# 328vusb.net
KiCad netlist of a schematic drawn in EAGLE
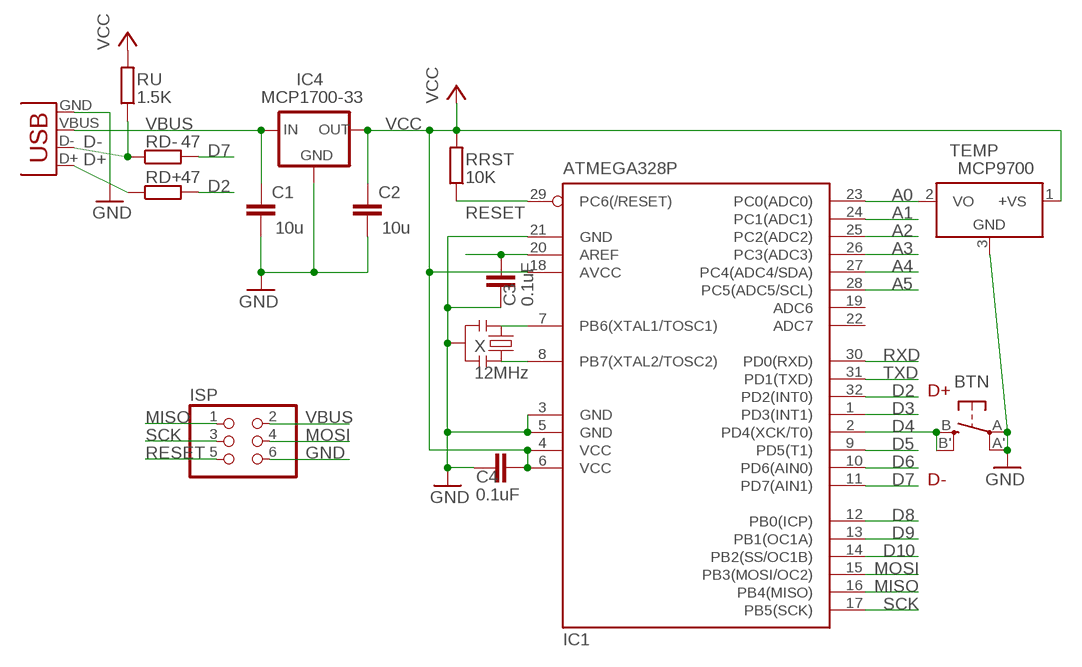
[diagram p0: schematic, sheet 1]

(export (version "E")
  (design (tool "Eeschema 10.0.6"))
  (components
    (comp (ref "BTN")
      (value "EVQQ2")
      (footprint "eagle-import:EVQ-Q2")
      (libsource (lib "eagle-import") (part "EVQQ2"))
    )
    (comp (ref "C1")
      (value "10u")
      (footprint "eagle-import:C0805")
      (libsource (lib "eagle-import") (part "resistor_C-EUC0805"))
    )
    (comp (ref "C2")
      (value "10u")
      (footprint "eagle-import:C0805")
      (libsource (lib "eagle-import") (part "resistor_C-EUC0805"))
    )
    (comp (ref "C3")
      (value "0.1uF")
      (footprint "eagle-import:C0805")
      (libsource (lib "eagle-import") (part "C-EUC0805"))
    )
    (comp (ref "C4")
      (value "0.1uF")
      (footprint "eagle-import:C0805")
      (libsource (lib "eagle-import") (part "C-EUC0805"))
    )
    (comp (ref "IC1")
      (value "ATMEGA328P")
      (footprint "eagle-import:TQFP32-08")
      (fields (field (name "MPN") "ATMEGA8-16AU"))
      (libsource (lib "eagle-import") (part "MEGA8-AI"))
    )
    (comp (ref "IC4")
      (value "MCP1700-33")
      (footprint "eagle-import:SOT23")
      (libsource (lib "eagle-import") (part "MCP1700SOT233"))
    )
    (comp (ref "ISP")
      (value "PINHD-2X3")
      (footprint "eagle-import:2X03")
      (libsource (lib "eagle-import") (part "PINHD-2X3"))
    )
    (comp (ref "RD+")
      (value "47")
      (footprint "eagle-import:R0805")
      (libsource (lib "eagle-import") (part "R-EU_R0805"))
    )
    (comp (ref "RD-")
      (value "47")
      (footprint "eagle-import:R0805")
      (libsource (lib "eagle-import") (part "R-EU_R0805"))
    )
    (comp (ref "RRST")
      (value "10K")
      (footprint "eagle-import:R0805")
      (libsource (lib "eagle-import") (part "R-EU_R0805"))
    )
    (comp (ref "RU")
      (value "1.5K")
      (footprint "eagle-import:R0805")
      (libsource (lib "eagle-import") (part "R-EU_R0805"))
    )
    (comp (ref "TEMP")
      (value "MCP9700")
      (footprint "eagle-import:SOT23")
      (libsource (lib "eagle-import") (part "LM50"))
    )
    (comp (ref "X")
      (value "12MHz")
      (footprint "eagle-import:RESONATOR-SMD")
      (libsource (lib "eagle-import") (part "RESONATORSMD"))
    )
    (comp (ref "X1")
      (value "USBSMD")
      (footprint "eagle-import:USB-MINIB")
      (libsource (lib "eagle-import") (part "USBSMD"))
    )
  )
  (nets
    (net (code "1") (name "/A0") (class "Default")
      (node (ref "IC1") (pin "23") (pinfunction "PC0(ADC0)_23") (pintype "bidirectional"))
      (node (ref "TEMP") (pin "2") (pinfunction "VO_2") (pintype "input"))
    )
    (net (code "2") (name "/A1") (class "Default")
      (node (ref "IC1") (pin "24") (pinfunction "PC1(ADC1)_24") (pintype "bidirectional"))
    )
    (net (code "3") (name "/A2") (class "Default")
      (node (ref "IC1") (pin "25") (pinfunction "PC2(ADC2)_25") (pintype "bidirectional"))
    )
    (net (code "4") (name "/A3") (class "Default")
      (node (ref "IC1") (pin "26") (pinfunction "PC3(ADC3)_26") (pintype "bidirectional"))
    )
    (net (code "5") (name "/A4") (class "Default")
      (node (ref "IC1") (pin "27") (pinfunction "PC4(ADC4/SDA)_27") (pintype "bidirectional"))
    )
    (net (code "6") (name "/A5") (class "Default")
      (node (ref "IC1") (pin "28") (pinfunction "PC5(ADC5/SCL)_28") (pintype "bidirectional"))
    )
    (net (code "7") (name "/D+") (class "Default")
      (node (ref "RD+") (pin "1") (pinfunction "1_1") (pintype "passive"))
      (node (ref "X1") (pin "D+") (pinfunction "D+_D+") (pintype "bidirectional"))
    )
    (net (code "8") (name "/D-") (class "Default")
      (node (ref "RD-") (pin "1") (pinfunction "1_1") (pintype "passive"))
      (node (ref "RU") (pin "1") (pinfunction "1_1") (pintype "passive"))
      (node (ref "X1") (pin "D-") (pinfunction "D-_D-") (pintype "bidirectional"))
    )
    (net (code "9") (name "/D2") (class "Default")
      (node (ref "IC1") (pin "32") (pinfunction "PD2(INT0)_32") (pintype "bidirectional"))
      (node (ref "RD+") (pin "2") (pinfunction "2_2") (pintype "passive"))
    )
    (net (code "10") (name "/D3") (class "Default")
      (node (ref "IC1") (pin "1") (pinfunction "PD3(INT1)_1") (pintype "bidirectional"))
    )
    (net (code "11") (name "/D4") (class "Default")
      (node (ref "BTN") (pin "B") (pinfunction "S_B") (pintype "passive"))
      (node (ref "BTN") (pin "B'") (pinfunction "S1_B'") (pintype "passive"))
      (node (ref "IC1") (pin "2") (pinfunction "PD4(XCK/T0)_2") (pintype "bidirectional"))
    )
    (net (code "12") (name "/D5") (class "Default")
      (node (ref "IC1") (pin "9") (pinfunction "PD5(T1)_9") (pintype "bidirectional"))
    )
    (net (code "13") (name "/D6") (class "Default")
      (node (ref "IC1") (pin "10") (pinfunction "PD6(AIN0)_10") (pintype "bidirectional"))
    )
    (net (code "14") (name "/D7") (class "Default")
      (node (ref "IC1") (pin "11") (pinfunction "PD7(AIN1)_11") (pintype "bidirectional"))
      (node (ref "RD-") (pin "2") (pinfunction "2_2") (pintype "passive"))
    )
    (net (code "15") (name "/D8") (class "Default")
      (node (ref "IC1") (pin "12") (pinfunction "PB0(ICP)_12") (pintype "bidirectional"))
    )
    (net (code "16") (name "/D9") (class "Default")
      (node (ref "IC1") (pin "13") (pinfunction "PB1(OC1A)_13") (pintype "bidirectional"))
    )
    (net (code "17") (name "/D10") (class "Default")
      (node (ref "IC1") (pin "14") (pinfunction "PB2(SS/OC1B)_14") (pintype "bidirectional"))
    )
    (net (code "18") (name "/MISO") (class "Default")
      (node (ref "IC1") (pin "16") (pinfunction "PB4(MISO)_16") (pintype "bidirectional"))
      (node (ref "ISP") (pin "1") (pinfunction "1_1") (pintype "passive"))
    )
    (net (code "19") (name "/MOSI") (class "Default")
      (node (ref "IC1") (pin "15") (pinfunction "PB3(MOSI/OC2)_15") (pintype "bidirectional"))
      (node (ref "ISP") (pin "4") (pinfunction "4_4") (pintype "passive"))
    )
    (net (code "20") (name "/RESET") (class "Default")
      (node (ref "IC1") (pin "29") (pinfunction "PC6(/RESET)_29") (pintype "bidirectional"))
      (node (ref "ISP") (pin "5") (pinfunction "5_5") (pintype "passive"))
      (node (ref "RRST") (pin "1") (pinfunction "1_1") (pintype "passive"))
    )
    (net (code "21") (name "/RXD") (class "Default")
      (node (ref "IC1") (pin "30") (pinfunction "PD0(RXD)_30") (pintype "bidirectional"))
    )
    (net (code "22") (name "/SCK") (class "Default")
      (node (ref "IC1") (pin "17") (pinfunction "PB5(SCK)_17") (pintype "bidirectional"))
      (node (ref "ISP") (pin "3") (pinfunction "3_3") (pintype "passive"))
    )
    (net (code "23") (name "/TXD") (class "Default")
      (node (ref "IC1") (pin "31") (pinfunction "PD1(TXD)_31") (pintype "bidirectional"))
    )
    (net (code "24") (name "/VBUS") (class "Default")
      (node (ref "C1") (pin "1") (pinfunction "1_1") (pintype "passive"))
      (node (ref "IC4") (pin "3") (pinfunction "IN_3") (pintype "input"))
      (node (ref "ISP") (pin "2") (pinfunction "2_2") (pintype "passive"))
      (node (ref "X1") (pin "VBUS") (pinfunction "VBUS_VBUS") (pintype "bidirectional"))
    )
    (net (code "25") (name "GND") (class "Default")
      (node (ref "BTN") (pin "A") (pinfunction "P_A") (pintype "passive"))
      (node (ref "BTN") (pin "A'") (pinfunction "P1_A'") (pintype "passive"))
      (node (ref "C1") (pin "2") (pinfunction "2_2") (pintype "passive"))
      (node (ref "C2") (pin "2") (pinfunction "2_2") (pintype "passive"))
      (node (ref "C3") (pin "1") (pinfunction "1_1") (pintype "passive"))
      (node (ref "C4") (pin "1") (pinfunction "1_1") (pintype "passive"))
      (node (ref "IC1") (pin "21") (pinfunction "GND_21") (pintype "power_in"))
      (node (ref "IC1") (pin "3") (pinfunction "GND_3") (pintype "power_in"))
      (node (ref "IC1") (pin "5") (pinfunction "GND_5") (pintype "power_in"))
      (node (ref "IC4") (pin "1") (pinfunction "GND_1") (pintype "input"))
      (node (ref "ISP") (pin "6") (pinfunction "6_6") (pintype "passive"))
      (node (ref "TEMP") (pin "3") (pinfunction "GND_3") (pintype "power_in"))
      (node (ref "X") (pin "2") (pinfunction "2_2") (pintype "passive"))
      (node (ref "X1") (pin "GND") (pinfunction "GND_GND") (pintype "bidirectional"))
    )
    (net (code "26") (name "Net-(IC1-AREF)") (class "Default")
      (node (ref "C3") (pin "2") (pinfunction "2_2") (pintype "passive"))
      (node (ref "IC1") (pin "20") (pinfunction "AREF_20") (pintype "passive"))
    )
    (net (code "27") (name "Net-(IC1-PB6(XTAL1{slash}TOSC1))") (class "Default")
      (node (ref "IC1") (pin "7") (pinfunction "PB6(XTAL1/TOSC1)_7") (pintype "bidirectional"))
      (node (ref "X") (pin "1") (pinfunction "1_1") (pintype "passive"))
    )
    (net (code "28") (name "Net-(IC1-PB7(XTAL2{slash}TOSC2))") (class "Default")
      (node (ref "IC1") (pin "8") (pinfunction "PB7(XTAL2/TOSC2)_8") (pintype "bidirectional"))
      (node (ref "X") (pin "3") (pinfunction "3_3") (pintype "passive"))
    )
    (net (code "29") (name "VCC") (class "Default")
      (node (ref "C2") (pin "1") (pinfunction "1_1") (pintype "passive"))
      (node (ref "C4") (pin "2") (pinfunction "2_2") (pintype "passive"))
      (node (ref "IC1") (pin "18") (pinfunction "AVCC_18") (pintype "power_in"))
      (node (ref "IC1") (pin "4") (pinfunction "VCC_4") (pintype "power_in"))
      (node (ref "IC1") (pin "6") (pinfunction "VCC_6") (pintype "power_in"))
      (node (ref "IC4") (pin "2") (pinfunction "OUT_2") (pintype "passive"))
      (node (ref "RRST") (pin "2") (pinfunction "2_2") (pintype "passive"))
      (node (ref "RU") (pin "2") (pinfunction "2_2") (pintype "passive"))
      (node (ref "TEMP") (pin "1") (pinfunction "+VS_1") (pintype "input"))
    )
    (net (code "30") (name "unconnected-(IC1-ADC6-Pad19)") (class "Default")
      (node (ref "IC1") (pin "19") (pinfunction "ADC6_19") (pintype "bidirectional"))
    )
    (net (code "31") (name "unconnected-(IC1-ADC7-Pad22)") (class "Default")
      (node (ref "IC1") (pin "22") (pinfunction "ADC7_22") (pintype "bidirectional"))
    )
  )
)
